# Adapter_v1_1B.net
KiCad netlist of a schematic drawn in EAGLE
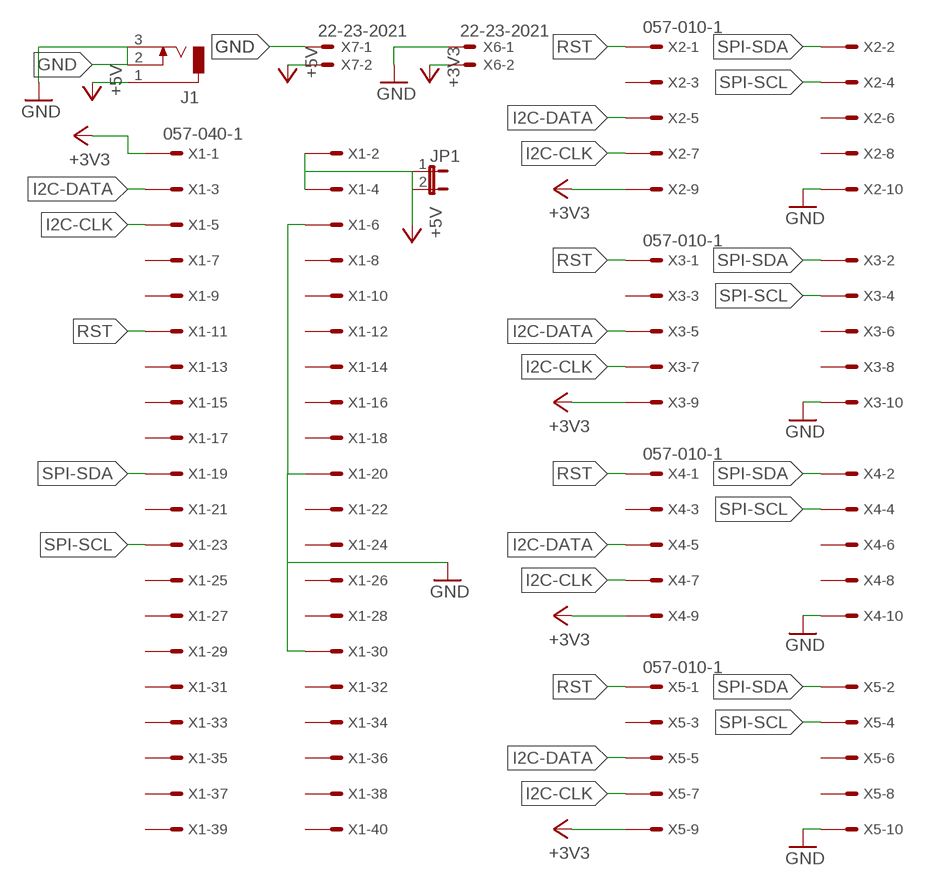
[diagram p0: schematic, sheet 1]

(export (version "E")
  (design (tool "Eeschema 10.0.6"))
  (components
    (comp (ref "J1")
      (value "DCJ0303")
      (footprint "eagle-import:DCJ0303")
      (libsource (lib "eagle-import") (part "DCJ0303"))
    )
    (comp (ref "JP1")
      (value "JP1E")
      (footprint "eagle-import:JP1")
      (libsource (lib "eagle-import") (part "JP1E"))
    )
    (comp (ref "X1")
      (value "057-040-1")
      (footprint "eagle-import:057-040-1")
      (libsource (lib "eagle-import") (part "057-040-1"))
    )
    (comp (ref "X2")
      (value "057-010-1")
      (footprint "eagle-import:057-010-1")
      (libsource (lib "eagle-import") (part "057-010-1"))
    )
    (comp (ref "X3")
      (value "057-010-1")
      (footprint "eagle-import:057-010-1")
      (libsource (lib "eagle-import") (part "057-010-1"))
    )
    (comp (ref "X4")
      (value "057-010-1")
      (footprint "eagle-import:057-010-1")
      (libsource (lib "eagle-import") (part "057-010-1"))
    )
    (comp (ref "X5")
      (value "057-010-1")
      (footprint "eagle-import:057-010-1")
      (libsource (lib "eagle-import") (part "057-010-1"))
    )
    (comp (ref "X6")
      (value "22-23-2021")
      (footprint "eagle-import:22-23-2021")
      (fields (field (name "MF") "MOLEX"))
      (libsource (lib "eagle-import") (part "22-23-2021"))
    )
    (comp (ref "X7")
      (value "22-23-2021")
      (footprint "eagle-import:22-23-2021")
      (fields (field (name "MF") "MOLEX"))
      (libsource (lib "eagle-import") (part "22-23-2021"))
    )
  )
  (nets
    (net (code "1") (name "+3V3") (class "Default")
      (node (ref "X1") (pin "1") (pinfunction "S_1") (pintype "passive"))
      (node (ref "X2") (pin "9") (pinfunction "S_9") (pintype "passive"))
      (node (ref "X3") (pin "9") (pinfunction "S_9") (pintype "passive"))
      (node (ref "X4") (pin "9") (pinfunction "S_9") (pintype "passive"))
      (node (ref "X5") (pin "9") (pinfunction "S_9") (pintype "passive"))
      (node (ref "X6") (pin "2") (pinfunction "S_2") (pintype "passive"))
    )
    (net (code "2") (name "+5V") (class "Default")
      (node (ref "J1") (pin "1") (pinfunction "1_1") (pintype "passive"))
      (node (ref "JP1") (pin "1") (pinfunction "1_1") (pintype "passive"))
      (node (ref "JP1") (pin "2") (pinfunction "2_2") (pintype "passive"))
      (node (ref "X1") (pin "2") (pinfunction "S_2") (pintype "passive"))
      (node (ref "X1") (pin "4") (pinfunction "S_4") (pintype "passive"))
      (node (ref "X7") (pin "2") (pinfunction "S_2") (pintype "passive"))
    )
    (net (code "3") (name "GND") (class "Default")
      (node (ref "J1") (pin "2") (pinfunction "2_2") (pintype "passive"))
      (node (ref "J1") (pin "3") (pinfunction "3_3") (pintype "passive"))
      (node (ref "X1") (pin "20") (pinfunction "S_20") (pintype "passive"))
      (node (ref "X1") (pin "30") (pinfunction "S_30") (pintype "passive"))
      (node (ref "X1") (pin "6") (pinfunction "S_6") (pintype "passive"))
      (node (ref "X2") (pin "10") (pinfunction "S_10") (pintype "passive"))
      (node (ref "X3") (pin "10") (pinfunction "S_10") (pintype "passive"))
      (node (ref "X4") (pin "10") (pinfunction "S_10") (pintype "passive"))
      (node (ref "X5") (pin "10") (pinfunction "S_10") (pintype "passive"))
      (node (ref "X6") (pin "1") (pinfunction "S_1") (pintype "passive"))
      (node (ref "X7") (pin "1") (pinfunction "S_1") (pintype "passive"))
    )
    (net (code "4") (name "I2C-CLK") (class "Default")
      (node (ref "X1") (pin "5") (pinfunction "S_5") (pintype "passive"))
      (node (ref "X2") (pin "7") (pinfunction "S_7") (pintype "passive"))
      (node (ref "X3") (pin "7") (pinfunction "S_7") (pintype "passive"))
      (node (ref "X4") (pin "7") (pinfunction "S_7") (pintype "passive"))
      (node (ref "X5") (pin "7") (pinfunction "S_7") (pintype "passive"))
    )
    (net (code "5") (name "I2C-DATA") (class "Default")
      (node (ref "X1") (pin "3") (pinfunction "S_3") (pintype "passive"))
      (node (ref "X2") (pin "5") (pinfunction "S_5") (pintype "passive"))
      (node (ref "X3") (pin "5") (pinfunction "S_5") (pintype "passive"))
      (node (ref "X4") (pin "5") (pinfunction "S_5") (pintype "passive"))
      (node (ref "X5") (pin "5") (pinfunction "S_5") (pintype "passive"))
    )
    (net (code "6") (name "RST") (class "Default")
      (node (ref "X1") (pin "11") (pinfunction "S_11") (pintype "passive"))
      (node (ref "X2") (pin "1") (pinfunction "S_1") (pintype "passive"))
      (node (ref "X3") (pin "1") (pinfunction "S_1") (pintype "passive"))
      (node (ref "X4") (pin "1") (pinfunction "S_1") (pintype "passive"))
      (node (ref "X5") (pin "1") (pinfunction "S_1") (pintype "passive"))
    )
    (net (code "7") (name "SPI-SCL") (class "Default")
      (node (ref "X1") (pin "23") (pinfunction "S_23") (pintype "passive"))
      (node (ref "X2") (pin "4") (pinfunction "S_4") (pintype "passive"))
      (node (ref "X3") (pin "4") (pinfunction "S_4") (pintype "passive"))
      (node (ref "X4") (pin "4") (pinfunction "S_4") (pintype "passive"))
      (node (ref "X5") (pin "4") (pinfunction "S_4") (pintype "passive"))
    )
    (net (code "8") (name "SPI-SDA") (class "Default")
      (node (ref "X1") (pin "19") (pinfunction "S_19") (pintype "passive"))
      (node (ref "X2") (pin "2") (pinfunction "S_2") (pintype "passive"))
      (node (ref "X3") (pin "2") (pinfunction "S_2") (pintype "passive"))
      (node (ref "X4") (pin "2") (pinfunction "S_2") (pintype "passive"))
      (node (ref "X5") (pin "2") (pinfunction "S_2") (pintype "passive"))
    )
    (net (code "9") (name "unconnected-(X1AA-S-Pad33)") (class "Default")
      (node (ref "X1") (pin "33") (pinfunction "S_33") (pintype "passive"))
    )
    (net (code "10") (name "unconnected-(X1AB-S-Pad34)") (class "Default")
      (node (ref "X1") (pin "34") (pinfunction "S_34") (pintype "passive"))
    )
    (net (code "11") (name "unconnected-(X1AC-S-Pad35)") (class "Default")
      (node (ref "X1") (pin "35") (pinfunction "S_35") (pintype "passive"))
    )
    (net (code "12") (name "unconnected-(X1AD-S-Pad36)") (class "Default")
      (node (ref "X1") (pin "36") (pinfunction "S_36") (pintype "passive"))
    )
    (net (code "13") (name "unconnected-(X1AE-S-Pad37)") (class "Default")
      (node (ref "X1") (pin "37") (pinfunction "S_37") (pintype "passive"))
    )
    (net (code "14") (name "unconnected-(X1AF-S-Pad38)") (class "Default")
      (node (ref "X1") (pin "38") (pinfunction "S_38") (pintype "passive"))
    )
    (net (code "15") (name "unconnected-(X1AG-S-Pad39)") (class "Default")
      (node (ref "X1") (pin "39") (pinfunction "S_39") (pintype "passive"))
    )
    (net (code "16") (name "unconnected-(X1AI-S-Pad40)") (class "Default")
      (node (ref "X1") (pin "40") (pinfunction "S_40") (pintype "passive"))
    )
    (net (code "17") (name "unconnected-(X1AL-S-Pad7)") (class "Default")
      (node (ref "X1") (pin "7") (pinfunction "S_7") (pintype "passive"))
    )
    (net (code "18") (name "unconnected-(X1AM-S-Pad8)") (class "Default")
      (node (ref "X1") (pin "8") (pinfunction "S_8") (pintype "passive"))
    )
    (net (code "19") (name "unconnected-(X1AN-S-Pad9)") (class "Default")
      (node (ref "X1") (pin "9") (pinfunction "S_9") (pintype "passive"))
    )
    (net (code "20") (name "unconnected-(X1B-S-Pad10)") (class "Default")
      (node (ref "X1") (pin "10") (pinfunction "S_10") (pintype "passive"))
    )
    (net (code "21") (name "unconnected-(X1D-S-Pad12)") (class "Default")
      (node (ref "X1") (pin "12") (pinfunction "S_12") (pintype "passive"))
    )
    (net (code "22") (name "unconnected-(X1E-S-Pad13)") (class "Default")
      (node (ref "X1") (pin "13") (pinfunction "S_13") (pintype "passive"))
    )
    (net (code "23") (name "unconnected-(X1F-S-Pad14)") (class "Default")
      (node (ref "X1") (pin "14") (pinfunction "S_14") (pintype "passive"))
    )
    (net (code "24") (name "unconnected-(X1G-S-Pad15)") (class "Default")
      (node (ref "X1") (pin "15") (pinfunction "S_15") (pintype "passive"))
    )
    (net (code "25") (name "unconnected-(X1H-S-Pad16)") (class "Default")
      (node (ref "X1") (pin "16") (pinfunction "S_16") (pintype "passive"))
    )
    (net (code "26") (name "unconnected-(X1I-S-Pad17)") (class "Default")
      (node (ref "X1") (pin "17") (pinfunction "S_17") (pintype "passive"))
    )
    (net (code "27") (name "unconnected-(X1J-S-Pad18)") (class "Default")
      (node (ref "X1") (pin "18") (pinfunction "S_18") (pintype "passive"))
    )
    (net (code "28") (name "unconnected-(X1N-S-Pad21)") (class "Default")
      (node (ref "X1") (pin "21") (pinfunction "S_21") (pintype "passive"))
    )
    (net (code "29") (name "unconnected-(X1O-S-Pad22)") (class "Default")
      (node (ref "X1") (pin "22") (pinfunction "S_22") (pintype "passive"))
    )
    (net (code "30") (name "unconnected-(X1Q-S-Pad24)") (class "Default")
      (node (ref "X1") (pin "24") (pinfunction "S_24") (pintype "passive"))
    )
    (net (code "31") (name "unconnected-(X1R-S-Pad25)") (class "Default")
      (node (ref "X1") (pin "25") (pinfunction "S_25") (pintype "passive"))
    )
    (net (code "32") (name "unconnected-(X1S-S-Pad26)") (class "Default")
      (node (ref "X1") (pin "26") (pinfunction "S_26") (pintype "passive"))
    )
    (net (code "33") (name "unconnected-(X1T-S-Pad27)") (class "Default")
      (node (ref "X1") (pin "27") (pinfunction "S_27") (pintype "passive"))
    )
    (net (code "34") (name "unconnected-(X1U-S-Pad28)") (class "Default")
      (node (ref "X1") (pin "28") (pinfunction "S_28") (pintype "passive"))
    )
    (net (code "35") (name "unconnected-(X1V-S-Pad29)") (class "Default")
      (node (ref "X1") (pin "29") (pinfunction "S_29") (pintype "passive"))
    )
    (net (code "36") (name "unconnected-(X1Y-S-Pad31)") (class "Default")
      (node (ref "X1") (pin "31") (pinfunction "S_31") (pintype "passive"))
    )
    (net (code "37") (name "unconnected-(X1Z-S-Pad32)") (class "Default")
      (node (ref "X1") (pin "32") (pinfunction "S_32") (pintype "passive"))
    )
    (net (code "38") (name "unconnected-(X2D-S-Pad3)") (class "Default")
      (node (ref "X2") (pin "3") (pinfunction "S_3") (pintype "passive"))
    )
    (net (code "39") (name "unconnected-(X2G-S-Pad6)") (class "Default")
      (node (ref "X2") (pin "6") (pinfunction "S_6") (pintype "passive"))
    )
    (net (code "40") (name "unconnected-(X2I-S-Pad8)") (class "Default")
      (node (ref "X2") (pin "8") (pinfunction "S_8") (pintype "passive"))
    )
    (net (code "41") (name "unconnected-(X3D-S-Pad3)") (class "Default")
      (node (ref "X3") (pin "3") (pinfunction "S_3") (pintype "passive"))
    )
    (net (code "42") (name "unconnected-(X3G-S-Pad6)") (class "Default")
      (node (ref "X3") (pin "6") (pinfunction "S_6") (pintype "passive"))
    )
    (net (code "43") (name "unconnected-(X3I-S-Pad8)") (class "Default")
      (node (ref "X3") (pin "8") (pinfunction "S_8") (pintype "passive"))
    )
    (net (code "44") (name "unconnected-(X4D-S-Pad3)") (class "Default")
      (node (ref "X4") (pin "3") (pinfunction "S_3") (pintype "passive"))
    )
    (net (code "45") (name "unconnected-(X4G-S-Pad6)") (class "Default")
      (node (ref "X4") (pin "6") (pinfunction "S_6") (pintype "passive"))
    )
    (net (code "46") (name "unconnected-(X4I-S-Pad8)") (class "Default")
      (node (ref "X4") (pin "8") (pinfunction "S_8") (pintype "passive"))
    )
    (net (code "47") (name "unconnected-(X5D-S-Pad3)") (class "Default")
      (node (ref "X5") (pin "3") (pinfunction "S_3") (pintype "passive"))
    )
    (net (code "48") (name "unconnected-(X5G-S-Pad6)") (class "Default")
      (node (ref "X5") (pin "6") (pinfunction "S_6") (pintype "passive"))
    )
    (net (code "49") (name "unconnected-(X5I-S-Pad8)") (class "Default")
      (node (ref "X5") (pin "8") (pinfunction "S_8") (pintype "passive"))
    )
  )
)
